# L-D5019-08.net
KiCad netlist of a schematic drawn in Altium Designer
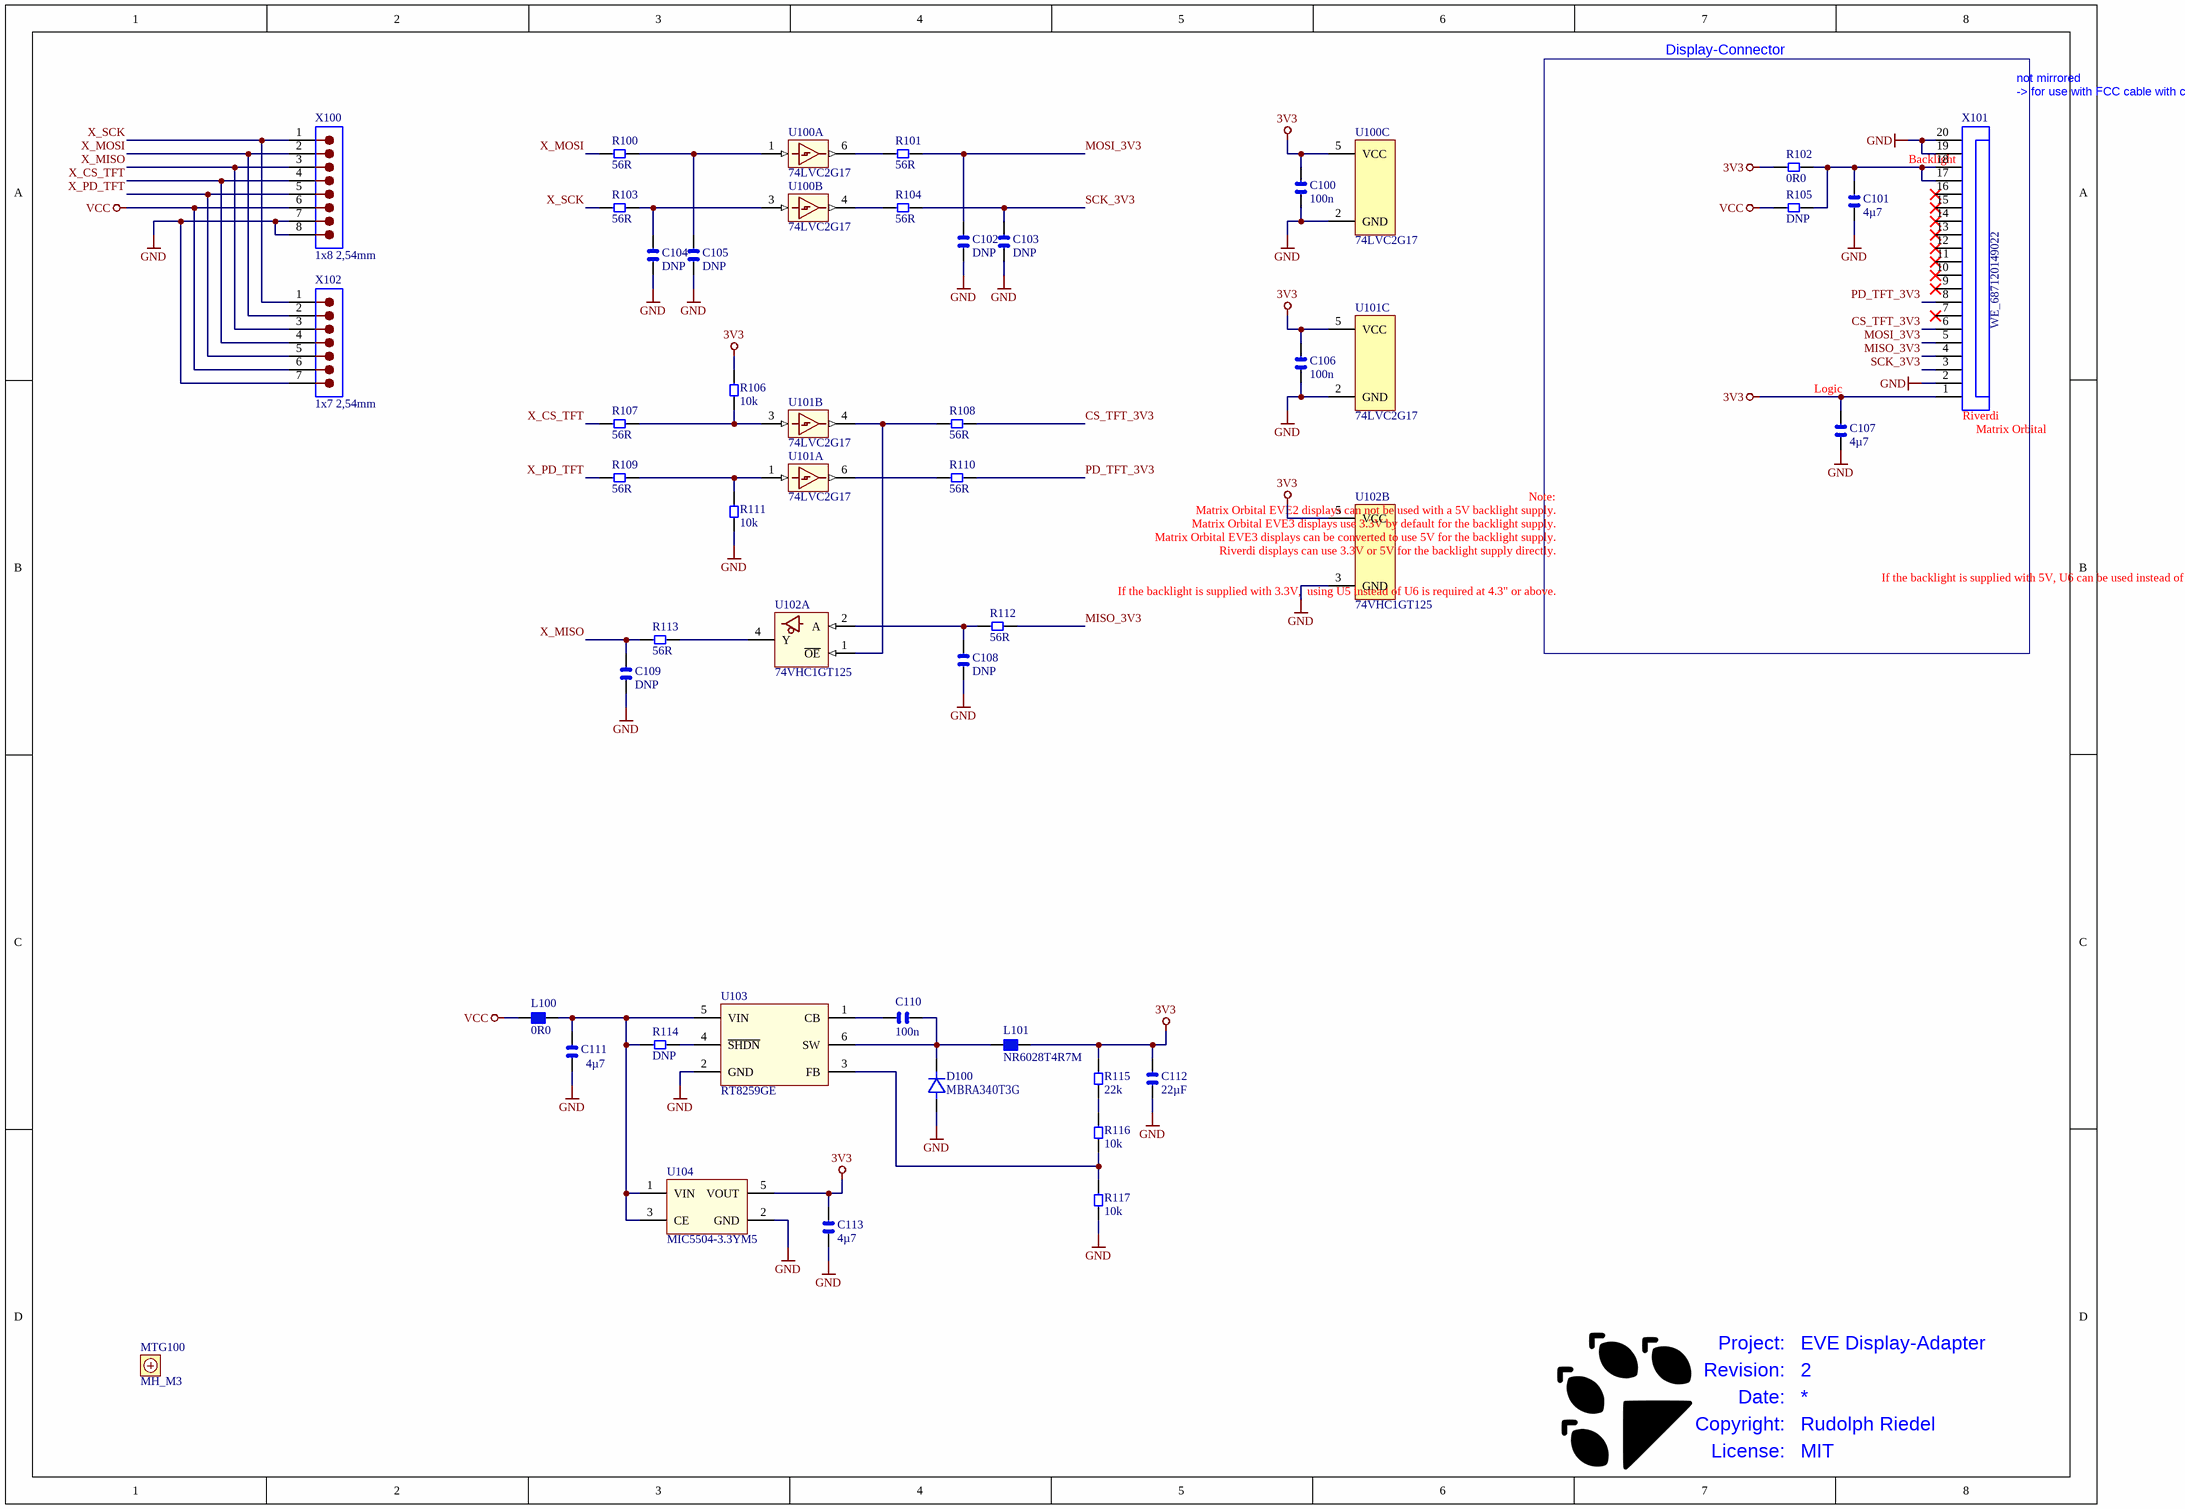
[diagram p0: L-D5019-08.SchDoc]

(export (version "E")
  (design (tool "Eeschema 10.0.6"))
  (components
    (comp (ref "C100")
      (value "100n")
      (footprint "CAPC2012X14L")
      (description "0805 Chip Capacitor")
      (fields (field (name "PART NUMBER") "CAPC_0805") (field (name "EDITOR") "rriedel"))
      (libsource (lib "HW-Labor_GF") (part "CAP_2_V2"))
    )
    (comp (ref "C101")
      (value "4µ7")
      (footprint "CAPC2012X14L")
      (description "0805 Chip Capacitor")
      (fields (field (name "PART NUMBER") "CAPC_0805") (field (name "ERSTELLER") "rriedel"))
      (libsource (lib "HW-Labor_GF") (part "CAP_2_V2"))
    )
    (comp (ref "C102")
      (value "DNP")
      (footprint "CAPC2012X14L")
      (description "0805 Chip Capacitor")
      (fields (field (name "PART NUMBER") "CAPC_0805") (field (name "EDITOR") "rriedel"))
      (libsource (lib "HW-Labor_GF") (part "CAP_2_V2"))
    )
    (comp (ref "C103")
      (value "DNP")
      (footprint "CAPC2012X14L")
      (description "0805 Chip Capacitor")
      (fields (field (name "PART NUMBER") "CAPC_0805") (field (name "EDITOR") "rriedel"))
      (libsource (lib "HW-Labor_GF") (part "CAP_2_V2"))
    )
    (comp (ref "C104")
      (value "DNP")
      (footprint "CAPC2012X14L")
      (description "0805 Chip Capacitor")
      (fields (field (name "PART NUMBER") "CAPC_0805") (field (name "EDITOR") "rriedel"))
      (libsource (lib "HW-Labor_GF") (part "CAP_2_V2"))
    )
    (comp (ref "C105")
      (value "DNP")
      (footprint "CAPC2012X14L")
      (description "0805 Chip Capacitor")
      (fields (field (name "PART NUMBER") "CAPC_0805") (field (name "EDITOR") "rriedel"))
      (libsource (lib "HW-Labor_GF") (part "CAP_2_V2"))
    )
    (comp (ref "C106")
      (value "100n")
      (footprint "CAPC2012X14L")
      (description "0805 Chip Capacitor")
      (fields (field (name "PART NUMBER") "CAPC_0805") (field (name "EDITOR") "rriedel"))
      (libsource (lib "HW-Labor_GF") (part "CAP_2_V2"))
    )
    (comp (ref "C107")
      (value "4µ7")
      (footprint "CAPC2012X14L")
      (description "0805 Chip Capacitor")
      (fields (field (name "PART NUMBER") "CAPC_0805") (field (name "ERSTELLER") "rriedel"))
      (libsource (lib "HW-Labor_GF") (part "CAP_2_V2"))
    )
    (comp (ref "C108")
      (value "DNP")
      (footprint "CAPC2012X14L")
      (description "0805 Chip Capacitor")
      (fields (field (name "PART NUMBER") "CAPC_0805") (field (name "EDITOR") "rriedel"))
      (libsource (lib "HW-Labor_GF") (part "CAP_2_V2"))
    )
    (comp (ref "C109")
      (value "DNP")
      (footprint "CAPC2012X14L")
      (description "0805 Chip Capacitor")
      (fields (field (name "PART NUMBER") "CAPC_0805") (field (name "EDITOR") "rriedel"))
      (libsource (lib "HW-Labor_GF") (part "CAP_2_V2"))
    )
    (comp (ref "C110")
      (value "100n")
      (footprint "CAPC2012X14L")
      (description "0805 Chip Capacitor")
      (fields (field (name "PART NUMBER") "CAPC_0805") (field (name "EDITOR") "rriedel"))
      (libsource (lib "HW-Labor_GF") (part "CAP_2_V2"))
    )
    (comp (ref "C111")
      (value "4µ7")
      (footprint "CAPC3216X19N")
      (description "1206 Chip Capacitor")
      (fields (field (name "PART NUMBER") "CAPC_1206") (field (name "EDITOR") "rriedel"))
      (libsource (lib "HW-Labor_GF") (part "CAP_2_V2"))
    )
    (comp (ref "C112")
      (value "22µF")
      (footprint "CAPC3216X19N")
      (description "1206 Chip Capacitor")
      (fields (field (name "PART NUMBER") "CAPC_1206") (field (name "EDITOR") "rriedel"))
      (libsource (lib "HW-Labor_GF") (part "CAP_2_V2"))
    )
    (comp (ref "C113")
      (value "4µ7")
      (footprint "CAPC2012X14L")
      (description "0805 Chip Capacitor")
      (fields (field (name "PART NUMBER") "CAPC_0805") (field (name "ERSTELLER") "rriedel"))
      (libsource (lib "HW-Labor_GF") (part "CAP_2_V2"))
    )
    (comp (ref "D100")
      (value "MBRA340T3G‎")
      (footprint "DIOM5226X23N")
      (description "Schottky Gleichrichterdiode, 40V / 3A / 450mV")
      (fields
        (field (name "MANUFACTURER") "ON Semiconductor")
        (field (name "DISTRIBUTOR_1_PART_NUMBER") "MBRA340T3GOSCT-ND")
        (field (name "EDITOR") "rriedel")
      )
      (libsource (lib "HW-Labor_GF") (part "Diode_A2_K1"))
    )
    (comp (ref "L100")
      (value "0R0")
      (footprint "INDC2012X10L")
      (description "0805 Chip Inductor")
      (fields (field (name "PART NUMBER") "INDC_0805") (field (name "EDITOR") "rriedel"))
      (libsource (lib "HW-Labor_GF") (part "IND_2_V1"))
    )
    (comp (ref "L101")
      (value "NR6028T4R7M")
      (footprint "TaiyoYuden_NR6028")
      (description "4,7µH, shielded, 2,7A, 40mR")
      (fields
        (field (name "MANUFACTURER") "Taiyo Yuden")
        (field (name "DISTRIBUTOR_1_PART_NUMBER") "587-2100-1-ND")
        (field (name "EDITOR") "rriedel")
      )
      (libsource (lib "HW-Labor_GF") (part "IND_2_V1"))
    )
    (comp (ref "MTG100")
      (value "MH_M3")
      (footprint "HOLE_3_2MM")
      (description "Mounting-Hole for M3 screws")
      (fields (field (name "EDITOR") "rriedel"))
      (libsource (lib "HW-Labor_GF") (part "MTG_V1"))
    )
    (comp (ref "R100")
      (value "56R")
      (footprint "RESC2012X06L")
      (description "0805 Chip Resistor")
      (fields (field (name "PART NUMBER") "RESC_0805") (field (name "EDITOR") "rriedel"))
      (libsource (lib "HW-Labor_GF") (part "RES_2_V2"))
    )
    (comp (ref "R101")
      (value "56R")
      (footprint "RESC2012X06L")
      (description "0805 Chip Resistor")
      (fields (field (name "PART NUMBER") "RESC_0805") (field (name "EDITOR") "rriedel"))
      (libsource (lib "HW-Labor_GF") (part "RES_2_V2"))
    )
    (comp (ref "R102")
      (value "0R0")
      (footprint "RESC2012X06L")
      (description "0805 Chip Resistor")
      (fields (field (name "PART NUMBER") "RESC_0805") (field (name "EDITOR") "rriedel"))
      (libsource (lib "HW-Labor_GF") (part "RES_2_V2"))
    )
    (comp (ref "R103")
      (value "56R")
      (footprint "RESC2012X06L")
      (description "0805 Chip Resistor")
      (fields (field (name "PART NUMBER") "RESC_0805") (field (name "EDITOR") "rriedel"))
      (libsource (lib "HW-Labor_GF") (part "RES_2_V2"))
    )
    (comp (ref "R104")
      (value "56R")
      (footprint "RESC2012X06L")
      (description "0805 Chip Resistor")
      (fields (field (name "PART NUMBER") "RESC_0805") (field (name "EDITOR") "rriedel"))
      (libsource (lib "HW-Labor_GF") (part "RES_2_V2"))
    )
    (comp (ref "R105")
      (value "DNP")
      (footprint "RESC2012X06L")
      (description "0805 Chip Resistor")
      (fields (field (name "PART NUMBER") "RESC_0805") (field (name "EDITOR") "rriedel"))
      (libsource (lib "HW-Labor_GF") (part "RES_2_V2"))
    )
    (comp (ref "R106")
      (value "10k")
      (footprint "RESC2012X06L")
      (description "0805 Chip Resistor")
      (fields (field (name "PART NUMBER") "RESC_0805") (field (name "EDITOR") "rriedel"))
      (libsource (lib "HW-Labor_GF") (part "RES_2_V2"))
    )
    (comp (ref "R107")
      (value "56R")
      (footprint "RESC2012X06L")
      (description "0805 Chip Resistor")
      (fields (field (name "PART NUMBER") "RESC_0805") (field (name "EDITOR") "rriedel"))
      (libsource (lib "HW-Labor_GF") (part "RES_2_V2"))
    )
    (comp (ref "R108")
      (value "56R")
      (footprint "RESC2012X06L")
      (description "0805 Chip Resistor")
      (fields (field (name "PART NUMBER") "RESC_0805") (field (name "EDITOR") "rriedel"))
      (libsource (lib "HW-Labor_GF") (part "RES_2_V2"))
    )
    (comp (ref "R109")
      (value "56R")
      (footprint "RESC2012X06L")
      (description "0805 Chip Resistor")
      (fields (field (name "PART NUMBER") "RESC_0805") (field (name "EDITOR") "rriedel"))
      (libsource (lib "HW-Labor_GF") (part "RES_2_V2"))
    )
    (comp (ref "R110")
      (value "56R")
      (footprint "RESC2012X06L")
      (description "0805 Chip Resistor")
      (fields (field (name "PART NUMBER") "RESC_0805") (field (name "EDITOR") "rriedel"))
      (libsource (lib "HW-Labor_GF") (part "RES_2_V2"))
    )
    (comp (ref "R111")
      (value "10k")
      (footprint "RESC2012X06L")
      (description "0805 Chip Resistor")
      (fields (field (name "PART NUMBER") "RESC_0805") (field (name "EDITOR") "rriedel"))
      (libsource (lib "HW-Labor_GF") (part "RES_2_V2"))
    )
    (comp (ref "R112")
      (value "56R")
      (footprint "RESC2012X06L")
      (description "0805 Chip Resistor")
      (fields (field (name "PART NUMBER") "RESC_0805") (field (name "EDITOR") "rriedel"))
      (libsource (lib "HW-Labor_GF") (part "RES_2_V2"))
    )
    (comp (ref "R113")
      (value "56R")
      (footprint "RESC2012X06L")
      (description "0805 Chip Resistor")
      (fields (field (name "PART NUMBER") "RESC_0805") (field (name "EDITOR") "rriedel"))
      (libsource (lib "HW-Labor_GF") (part "RES_2_V2"))
    )
    (comp (ref "R114")
      (value "DNP")
      (footprint "RESC2012X06L")
      (description "0805 Chip Resistor")
      (fields (field (name "PART NUMBER") "RESC_0805") (field (name "EDITOR") "rriedel"))
      (libsource (lib "HW-Labor_GF") (part "RES_2_V2"))
    )
    (comp (ref "R115")
      (value "22k")
      (footprint "RESC2012X06L")
      (description "0805 Chip Resistor")
      (fields (field (name "PART NUMBER") "RESC_0805") (field (name "EDITOR") "rriedel"))
      (libsource (lib "HW-Labor_GF") (part "RES_2_V2"))
    )
    (comp (ref "R116")
      (value "10k")
      (footprint "RESC2012X06L")
      (description "0805 Chip Resistor")
      (fields (field (name "PART NUMBER") "RESC_0805") (field (name "EDITOR") "rriedel"))
      (libsource (lib "HW-Labor_GF") (part "RES_2_V2"))
    )
    (comp (ref "R117")
      (value "10k")
      (footprint "RESC2012X06L")
      (description "0805 Chip Resistor")
      (fields (field (name "PART NUMBER") "RESC_0805") (field (name "EDITOR") "rriedel"))
      (libsource (lib "HW-Labor_GF") (part "RES_2_V2"))
    )
    (comp (ref "U100")
      (value "74LVC2G17")
      (footprint "SOT95P280X110-6N")
      (description "Dual Schmitt-Trigger Buffer with 5.5V tolerant inputs")
      (fields
        (field (name "MANUFACTURER") "TI")
        (field (name "DISTRIBUTOR_1_PART_NUMBER") "296-SN74LVC2G17DBVRCT-ND‎")
        (field (name "EDITOR") "rriedel")
      )
      (libsource (lib "HW-Labor_GF") (part "74LVC2G17"))
    )
    (comp (ref "U101")
      (value "74LVC2G17")
      (footprint "SOT95P280X110-6N")
      (description "Dual Schmitt-Trigger Buffer with 5.5V tolerant inputs")
      (fields
        (field (name "MANUFACTURER") "TI")
        (field (name "DISTRIBUTOR_1_PART_NUMBER") "296-SN74LVC2G17DBVRCT-ND‎")
        (field (name "EDITOR") "rriedel")
      )
      (libsource (lib "HW-Labor_GF") (part "74LVC2G17"))
    )
    (comp (ref "U102")
      (value "74VHC1GT125")
      (footprint "SOT95P280X110-5N")
      (description "1x Buffer with OE; 3-state,Level Shifter 3,3V to 5V and 5V to 3.3V")
      (fields
        (field (name "MANUFACTURER") "ON Semiconductor")
        (field (name "DISTRIBUTOR_1_PART_NUMBER") "1703291")
        (field (name "EDITOR") "rriedel")
      )
      (libsource (lib "HW-Labor_GF") (part "74LVC1G125G"))
    )
    (comp (ref "U103")
      (value "RT8259GE")
      (footprint "SOT95P280X110-6N")
      (description "Step-Down DC/DC Regulator, 24V, 1.2A, 1,4MHz")
      (fields
        (field (name "MANUFACTURER") "Richtek")
        (field (name "DISTRIBUTOR_1_PART_NUMBER") "1028-1497-1-ND")
        (field (name "EDITOR") "rriedel")
      )
      (libsource (lib "HW-Labor_GF") (part "StepDown_SOT23-6"))
    )
    (comp (ref "U104")
      (value "MIC5504-3.3YM5")
      (footprint "SOT95P280X110-5N")
      (description "300 mA LDO,  Vin=2,5V…5,5V, Vout= 3,3V, -40°C..125°C")
      (fields
        (field (name "MANUFACTURER") "Microchip")
        (field (name "DISTRIBUTOR_1_PART_NUMBER") "2510377")
        (field (name "EDITOR") "rriedel")
      )
      (libsource (lib "HW-Labor_GF") (part "LDO_SOT23-5"))
    )
    (comp (ref "X100")
      (value "1x8 2,54mm")
      (footprint "PINH_1x08_2_54mm")
      (description "Pin-Header 2,54 mm 8pins")
      (fields (field (name "PART NUMBER") "PINH_1x8_2_54") (field (name "EDITOR") "rriedel"))
      (libsource (lib "HW-Labor_GF") (part "CONM_1x8_V2"))
    )
    (comp (ref "X101")
      (value "WE_687120149022")
      (footprint "WE_687120149022")
      (description "20pin WR-FPC 0.50 mm SMT ZIF Horizontal - Bottom Contact")
      (fields
        (field (name "MANUFACTURER") "Wuerth")
        (field (name "DISTRIBUTOR_1_PART_NUMBER") "732-6002-1-ND")
        (field (name "EDITOR") "rriedel")
      )
      (libsource (lib "HW-Labor_GF") (part "FPC_20"))
    )
    (comp (ref "X102")
      (value "1x7 2,54mm")
      (footprint "PINH_1x07_2_54mm")
      (description "Pin-Header 2,54 mm 7pins")
      (fields (field (name "PART NUMBER") "PINH_1x7_2_54") (field (name "EDITOR") "rriedel"))
      (libsource (lib "HW-Labor_GF") (part "CONM_1x7_V2"))
    )
  )
  (nets
    (net (code "1") (name "/CS_TFT_3V3") (class "Default")
      (node (ref "R108") (pin "2") (pinfunction "2_2") (pintype "passive"))
      (node (ref "X101") (pin "6") (pinfunction "6_6") (pintype "passive"))
    )
    (net (code "2") (name "/MISO_3V3") (class "Default")
      (node (ref "R112") (pin "2") (pinfunction "2_2") (pintype "passive"))
      (node (ref "X101") (pin "4") (pinfunction "4_4") (pintype "passive"))
    )
    (net (code "3") (name "/MOSI_3V3") (class "Default")
      (node (ref "C102") (pin "2") (pinfunction "2_2") (pintype "passive"))
      (node (ref "R101") (pin "2") (pinfunction "2_2") (pintype "passive"))
      (node (ref "X101") (pin "5") (pinfunction "5_5") (pintype "passive"))
    )
    (net (code "4") (name "/PD_TFT_3V3") (class "Default")
      (node (ref "R110") (pin "2") (pinfunction "2_2") (pintype "passive"))
      (node (ref "X101") (pin "8") (pinfunction "8_8") (pintype "passive"))
    )
    (net (code "5") (name "/SCK_3V3") (class "Default")
      (node (ref "C103") (pin "2") (pinfunction "2_2") (pintype "passive"))
      (node (ref "R104") (pin "2") (pinfunction "2_2") (pintype "passive"))
      (node (ref "X101") (pin "3") (pinfunction "3_3") (pintype "passive"))
    )
    (net (code "6") (name "/X_CS_TFT") (class "Default")
      (node (ref "R107") (pin "1") (pinfunction "1_1") (pintype "passive"))
      (node (ref "X100") (pin "4") (pinfunction "4_4") (pintype "passive"))
      (node (ref "X102") (pin "4") (pinfunction "4_4") (pintype "passive"))
    )
    (net (code "7") (name "/X_MISO") (class "Default")
      (node (ref "C109") (pin "2") (pinfunction "2_2") (pintype "passive"))
      (node (ref "R113") (pin "1") (pinfunction "1_1") (pintype "passive"))
      (node (ref "X100") (pin "3") (pinfunction "3_3") (pintype "passive"))
      (node (ref "X102") (pin "3") (pinfunction "3_3") (pintype "passive"))
    )
    (net (code "8") (name "/X_MOSI") (class "Default")
      (node (ref "R100") (pin "1") (pinfunction "1_1") (pintype "passive"))
      (node (ref "X100") (pin "2") (pinfunction "2_2") (pintype "passive"))
      (node (ref "X102") (pin "2") (pinfunction "2_2") (pintype "passive"))
    )
    (net (code "9") (name "/X_PD_TFT") (class "Default")
      (node (ref "R109") (pin "1") (pinfunction "1_1") (pintype "passive"))
      (node (ref "X100") (pin "5") (pinfunction "5_5") (pintype "passive"))
      (node (ref "X102") (pin "5") (pinfunction "5_5") (pintype "passive"))
    )
    (net (code "10") (name "/X_SCK") (class "Default")
      (node (ref "R103") (pin "1") (pinfunction "1_1") (pintype "passive"))
      (node (ref "X100") (pin "1") (pinfunction "1_1") (pintype "passive"))
      (node (ref "X102") (pin "1") (pinfunction "1_1") (pintype "passive"))
    )
    (net (code "11") (name "3V3") (class "Default")
      (node (ref "C100") (pin "2") (pinfunction "2_2") (pintype "passive"))
      (node (ref "C106") (pin "2") (pinfunction "2_2") (pintype "passive"))
      (node (ref "C107") (pin "2") (pinfunction "2_2") (pintype "passive"))
      (node (ref "C112") (pin "2") (pinfunction "2_2") (pintype "passive"))
      (node (ref "C113") (pin "2") (pinfunction "2_2") (pintype "passive"))
      (node (ref "L101") (pin "2") (pinfunction "2_2") (pintype "passive"))
      (node (ref "R102") (pin "1") (pinfunction "1_1") (pintype "passive"))
      (node (ref "R106") (pin "2") (pinfunction "2_2") (pintype "passive"))
      (node (ref "R115") (pin "2") (pinfunction "2_2") (pintype "passive"))
      (node (ref "U100") (pin "5") (pinfunction "VCC_5") (pintype "power_in"))
      (node (ref "U101") (pin "5") (pinfunction "VCC_5") (pintype "power_in"))
      (node (ref "U102") (pin "5") (pinfunction "VCC_5") (pintype "passive"))
      (node (ref "U104") (pin "5") (pinfunction "VOUT_5") (pintype "passive"))
      (node (ref "X101") (pin "1") (pinfunction "1_1") (pintype "passive"))
    )
    (net (code "12") (name "GND") (class "Default")
      (node (ref "C100") (pin "1") (pinfunction "1_1") (pintype "passive"))
      (node (ref "C101") (pin "1") (pinfunction "1_1") (pintype "passive"))
      (node (ref "C102") (pin "1") (pinfunction "1_1") (pintype "passive"))
      (node (ref "C103") (pin "1") (pinfunction "1_1") (pintype "passive"))
      (node (ref "C104") (pin "1") (pinfunction "1_1") (pintype "passive"))
      (node (ref "C105") (pin "1") (pinfunction "1_1") (pintype "passive"))
      (node (ref "C106") (pin "1") (pinfunction "1_1") (pintype "passive"))
      (node (ref "C107") (pin "1") (pinfunction "1_1") (pintype "passive"))
      (node (ref "C108") (pin "1") (pinfunction "1_1") (pintype "passive"))
      (node (ref "C109") (pin "1") (pinfunction "1_1") (pintype "passive"))
      (node (ref "C111") (pin "1") (pinfunction "1_1") (pintype "passive"))
      (node (ref "C112") (pin "1") (pinfunction "1_1") (pintype "passive"))
      (node (ref "C113") (pin "1") (pinfunction "1_1") (pintype "passive"))
      (node (ref "D100") (pin "2") (pinfunction "2_2") (pintype "passive"))
      (node (ref "R111") (pin "1") (pinfunction "1_1") (pintype "passive"))
      (node (ref "R117") (pin "1") (pinfunction "1_1") (pintype "passive"))
      (node (ref "U100") (pin "2") (pinfunction "GND_2") (pintype "power_in"))
      (node (ref "U101") (pin "2") (pinfunction "GND_2") (pintype "power_in"))
      (node (ref "U102") (pin "3") (pinfunction "GND_3") (pintype "passive"))
      (node (ref "U103") (pin "2") (pinfunction "GND_2") (pintype "power_in"))
      (node (ref "U104") (pin "2") (pinfunction "GND_2") (pintype "passive"))
      (node (ref "X100") (pin "7") (pinfunction "7_7") (pintype "passive"))
      (node (ref "X100") (pin "8") (pinfunction "8_8") (pintype "passive"))
      (node (ref "X101") (pin "19") (pinfunction "19_19") (pintype "passive"))
      (node (ref "X101") (pin "2") (pinfunction "2_2") (pintype "passive"))
      (node (ref "X101") (pin "20") (pinfunction "20_20") (pintype "passive"))
      (node (ref "X102") (pin "7") (pinfunction "7_7") (pintype "passive"))
    )
    (net (code "13") (name "Net-(C101-Pad2)") (class "Default")
      (node (ref "C101") (pin "2") (pinfunction "2_2") (pintype "passive"))
      (node (ref "R102") (pin "2") (pinfunction "2_2") (pintype "passive"))
      (node (ref "R105") (pin "2") (pinfunction "2_2") (pintype "passive"))
      (node (ref "X101") (pin "17") (pinfunction "17_17") (pintype "passive"))
      (node (ref "X101") (pin "18") (pinfunction "18_18") (pintype "passive"))
    )
    (net (code "14") (name "Net-(R115-Pad1)") (class "Default")
      (node (ref "R115") (pin "1") (pinfunction "1_1") (pintype "passive"))
      (node (ref "R116") (pin "2") (pinfunction "2_2") (pintype "passive"))
    )
    (net (code "15") (name "Net-(U100A-1A)") (class "Default")
      (node (ref "C105") (pin "2") (pinfunction "2_2") (pintype "passive"))
      (node (ref "R100") (pin "2") (pinfunction "2_2") (pintype "passive"))
      (node (ref "U100") (pin "1") (pinfunction "1A_1") (pintype "input"))
    )
    (net (code "16") (name "Net-(U100A-1Y)") (class "Default")
      (node (ref "R101") (pin "1") (pinfunction "1_1") (pintype "passive"))
      (node (ref "U100") (pin "6") (pinfunction "1Y_6") (pintype "output"))
    )
    (net (code "17") (name "Net-(U100B-2A)") (class "Default")
      (node (ref "C104") (pin "2") (pinfunction "2_2") (pintype "passive"))
      (node (ref "R103") (pin "2") (pinfunction "2_2") (pintype "passive"))
      (node (ref "U100") (pin "3") (pinfunction "2A_3") (pintype "input"))
    )
    (net (code "18") (name "Net-(U100B-2Y)") (class "Default")
      (node (ref "R104") (pin "1") (pinfunction "1_1") (pintype "passive"))
      (node (ref "U100") (pin "4") (pinfunction "2Y_4") (pintype "output"))
    )
    (net (code "19") (name "Net-(U101A-1A)") (class "Default")
      (node (ref "R109") (pin "2") (pinfunction "2_2") (pintype "passive"))
      (node (ref "R111") (pin "2") (pinfunction "2_2") (pintype "passive"))
      (node (ref "U101") (pin "1") (pinfunction "1A_1") (pintype "input"))
    )
    (net (code "20") (name "Net-(U101A-1Y)") (class "Default")
      (node (ref "R110") (pin "1") (pinfunction "1_1") (pintype "passive"))
      (node (ref "U101") (pin "6") (pinfunction "1Y_6") (pintype "output"))
    )
    (net (code "21") (name "Net-(U101B-2A)") (class "Default")
      (node (ref "R106") (pin "1") (pinfunction "1_1") (pintype "passive"))
      (node (ref "R107") (pin "2") (pinfunction "2_2") (pintype "passive"))
      (node (ref "U101") (pin "3") (pinfunction "2A_3") (pintype "input"))
    )
    (net (code "22") (name "Net-(U101B-2Y)") (class "Default")
      (node (ref "R108") (pin "1") (pinfunction "1_1") (pintype "passive"))
      (node (ref "U101") (pin "4") (pinfunction "2Y_4") (pintype "output"))
      (node (ref "U102") (pin "1") (pinfunction "~{OE}_1") (pintype "input"))
    )
    (net (code "23") (name "Net-(U102A-A)") (class "Default")
      (node (ref "C108") (pin "2") (pinfunction "2_2") (pintype "passive"))
      (node (ref "R112") (pin "1") (pinfunction "1_1") (pintype "passive"))
      (node (ref "U102") (pin "2") (pinfunction "A_2") (pintype "input"))
    )
    (net (code "24") (name "Net-(U102A-Y)") (class "Default")
      (node (ref "R113") (pin "2") (pinfunction "2_2") (pintype "passive"))
      (node (ref "U102") (pin "4") (pinfunction "Y_4") (pintype "tri_state"))
    )
    (net (code "25") (name "Net-(U103-CB)") (class "Default")
      (node (ref "C110") (pin "1") (pinfunction "1_1") (pintype "passive"))
      (node (ref "U103") (pin "1") (pinfunction "CB_1") (pintype "passive"))
    )
    (net (code "26") (name "Net-(U103-FB)") (class "Default")
      (node (ref "R116") (pin "1") (pinfunction "1_1") (pintype "passive"))
      (node (ref "R117") (pin "2") (pinfunction "2_2") (pintype "passive"))
      (node (ref "U103") (pin "3") (pinfunction "FB_3") (pintype "passive"))
    )
    (net (code "27") (name "Net-(U103-SW)") (class "Default")
      (node (ref "C110") (pin "2") (pinfunction "2_2") (pintype "passive"))
      (node (ref "D100") (pin "1") (pinfunction "1_1") (pintype "passive"))
      (node (ref "L101") (pin "1") (pinfunction "1_1") (pintype "passive"))
      (node (ref "U103") (pin "6") (pinfunction "SW_6") (pintype "passive"))
    )
    (net (code "28") (name "Net-(U103-VIN)") (class "Default")
      (node (ref "C111") (pin "2") (pinfunction "2_2") (pintype "passive"))
      (node (ref "L100") (pin "2") (pinfunction "2_2") (pintype "passive"))
      (node (ref "R114") (pin "1") (pinfunction "1_1") (pintype "passive"))
      (node (ref "U103") (pin "5") (pinfunction "VIN_5") (pintype "power_in"))
      (node (ref "U104") (pin "1") (pinfunction "VIN_1") (pintype "passive"))
      (node (ref "U104") (pin "3") (pinfunction "CE_3") (pintype "passive"))
    )
    (net (code "29") (name "Net-(U103-~{SHDN})") (class "Default")
      (node (ref "R114") (pin "2") (pinfunction "2_2") (pintype "passive"))
      (node (ref "U103") (pin "4") (pinfunction "~{SHDN}_4") (pintype "passive"))
    )
    (net (code "30") (name "VCC") (class "Default")
      (node (ref "L100") (pin "1") (pinfunction "1_1") (pintype "passive"))
      (node (ref "R105") (pin "1") (pinfunction "1_1") (pintype "passive"))
      (node (ref "X100") (pin "6") (pinfunction "6_6") (pintype "passive"))
      (node (ref "X102") (pin "6") (pinfunction "6_6") (pintype "passive"))
    )
    (net (code "31") (name "unconnected-(X101-Pad7)") (class "Default")
      (node (ref "X101") (pin "7") (pinfunction "7_7") (pintype "passive+no_connect"))
    )
    (net (code "32") (name "unconnected-(X101-Pad9)") (class "Default")
      (node (ref "X101") (pin "9") (pinfunction "9_9") (pintype "passive+no_connect"))
    )
    (net (code "33") (name "unconnected-(X101-Pad10)") (class "Default")
      (node (ref "X101") (pin "10") (pinfunction "10_10") (pintype "passive+no_connect"))
    )
    (net (code "34") (name "unconnected-(X101-Pad11)") (class "Default")
      (node (ref "X101") (pin "11") (pinfunction "11_11") (pintype "passive+no_connect"))
    )
    (net (code "35") (name "unconnected-(X101-Pad12)") (class "Default")
      (node (ref "X101") (pin "12") (pinfunction "12_12") (pintype "passive+no_connect"))
    )
    (net (code "36") (name "unconnected-(X101-Pad13)") (class "Default")
      (node (ref "X101") (pin "13") (pinfunction "13_13") (pintype "passive+no_connect"))
    )
    (net (code "37") (name "unconnected-(X101-Pad14)") (class "Default")
      (node (ref "X101") (pin "14") (pinfunction "14_14") (pintype "passive+no_connect"))
    )
    (net (code "38") (name "unconnected-(X101-Pad15)") (class "Default")
      (node (ref "X101") (pin "15") (pinfunction "15_15") (pintype "passive+no_connect"))
    )
    (net (code "39") (name "unconnected-(X101-Pad16)") (class "Default")
      (node (ref "X101") (pin "16") (pinfunction "16_16") (pintype "passive+no_connect"))
    )
  )
)
